# raspi.net
KiCad netlist of a schematic drawn in EAGLE
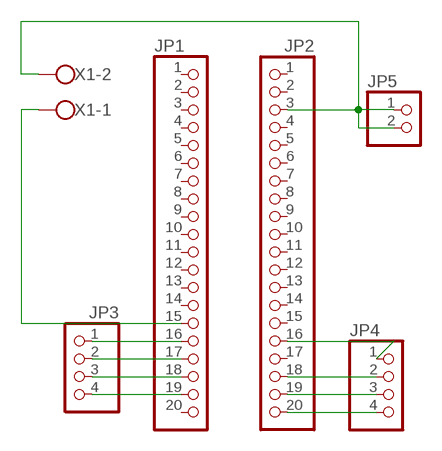
[diagram p0: schematic, sheet 1]

(export (version "E")
  (design (tool "Eeschema 10.0.6"))
  (components
    (comp (ref "JP1")
      (value "PINHD-1X20")
      (footprint "eagle-import:1X20")
      (libsource (lib "eagle-import") (part "PINHD-1X20"))
    )
    (comp (ref "JP2")
      (value "PINHD-1X20")
      (footprint "eagle-import:1X20")
      (libsource (lib "eagle-import") (part "PINHD-1X20"))
    )
    (comp (ref "JP3")
      (value "PINHD-1X4")
      (footprint "eagle-import:1X04")
      (libsource (lib "eagle-import") (part "PINHD-1X4"))
    )
    (comp (ref "JP4")
      (value "PINHD-1X4")
      (footprint "eagle-import:1X04")
      (libsource (lib "eagle-import") (part "PINHD-1X4"))
    )
    (comp (ref "JP5")
      (value "PINHD-1X2")
      (footprint "eagle-import:1X02")
      (libsource (lib "eagle-import") (part "PINHD-1X2"))
    )
    (comp (ref "X1")
      (value "W237-102")
      (footprint "eagle-import:W237-102")
      (fields (field (name "MPN") "237-102"))
      (libsource (lib "eagle-import") (part "W237-102"))
    )
  )
  (nets
    (net (code "1") (name "Net-(JP1-Pad16)") (class "Default")
      (node (ref "JP1") (pin "16") (pinfunction "16_16") (pintype "passive"))
      (node (ref "JP3") (pin "1") (pinfunction "1_1") (pintype "passive"))
    )
    (net (code "2") (name "Net-(JP1-Pad17)") (class "Default")
      (node (ref "JP1") (pin "17") (pinfunction "17_17") (pintype "passive"))
      (node (ref "JP3") (pin "2") (pinfunction "2_2") (pintype "passive"))
    )
    (net (code "3") (name "Net-(JP1-Pad18)") (class "Default")
      (node (ref "JP1") (pin "18") (pinfunction "18_18") (pintype "passive"))
      (node (ref "JP3") (pin "3") (pinfunction "3_3") (pintype "passive"))
    )
    (net (code "4") (name "Net-(JP1-Pad19)") (class "Default")
      (node (ref "JP1") (pin "19") (pinfunction "19_19") (pintype "passive"))
      (node (ref "JP3") (pin "4") (pinfunction "4_4") (pintype "passive"))
    )
    (net (code "5") (name "Net-(JP2-Pad16)") (class "Default")
      (node (ref "JP2") (pin "16") (pinfunction "16_16") (pintype "passive"))
      (node (ref "JP4") (pin "1") (pinfunction "1_1") (pintype "passive"))
    )
    (net (code "6") (name "Net-(JP2-Pad18)") (class "Default")
      (node (ref "JP2") (pin "18") (pinfunction "18_18") (pintype "passive"))
      (node (ref "JP4") (pin "2") (pinfunction "2_2") (pintype "passive"))
    )
    (net (code "7") (name "Net-(JP2-Pad19)") (class "Default")
      (node (ref "JP2") (pin "19") (pinfunction "19_19") (pintype "passive"))
      (node (ref "JP4") (pin "3") (pinfunction "3_3") (pintype "passive"))
    )
    (net (code "8") (name "Net-(JP2-Pad20)") (class "Default")
      (node (ref "JP2") (pin "20") (pinfunction "20_20") (pintype "passive"))
      (node (ref "JP4") (pin "4") (pinfunction "4_4") (pintype "passive"))
    )
    (net (code "9") (name "Net-(X1A-KL)") (class "Default")
      (node (ref "JP1") (pin "15") (pinfunction "15_15") (pintype "passive"))
      (node (ref "X1") (pin "1") (pinfunction "KL_1") (pintype "passive"))
    )
    (net (code "10") (name "Net-(X1B-KL)") (class "Default")
      (node (ref "JP2") (pin "3") (pinfunction "3_3") (pintype "passive"))
      (node (ref "JP5") (pin "1") (pinfunction "1_1") (pintype "passive"))
      (node (ref "JP5") (pin "2") (pinfunction "2_2") (pintype "passive"))
      (node (ref "X1") (pin "2") (pinfunction "KL_2") (pintype "passive"))
    )
    (net (code "11") (name "unconnected-(JP1-Pad1)") (class "Default")
      (node (ref "JP1") (pin "1") (pinfunction "1_1") (pintype "passive"))
    )
    (net (code "12") (name "unconnected-(JP1-Pad2)") (class "Default")
      (node (ref "JP1") (pin "2") (pinfunction "2_2") (pintype "passive"))
    )
    (net (code "13") (name "unconnected-(JP1-Pad3)") (class "Default")
      (node (ref "JP1") (pin "3") (pinfunction "3_3") (pintype "passive"))
    )
    (net (code "14") (name "unconnected-(JP1-Pad4)") (class "Default")
      (node (ref "JP1") (pin "4") (pinfunction "4_4") (pintype "passive"))
    )
    (net (code "15") (name "unconnected-(JP1-Pad5)") (class "Default")
      (node (ref "JP1") (pin "5") (pinfunction "5_5") (pintype "passive"))
    )
    (net (code "16") (name "unconnected-(JP1-Pad6)") (class "Default")
      (node (ref "JP1") (pin "6") (pinfunction "6_6") (pintype "passive"))
    )
    (net (code "17") (name "unconnected-(JP1-Pad7)") (class "Default")
      (node (ref "JP1") (pin "7") (pinfunction "7_7") (pintype "passive"))
    )
    (net (code "18") (name "unconnected-(JP1-Pad8)") (class "Default")
      (node (ref "JP1") (pin "8") (pinfunction "8_8") (pintype "passive"))
    )
    (net (code "19") (name "unconnected-(JP1-Pad9)") (class "Default")
      (node (ref "JP1") (pin "9") (pinfunction "9_9") (pintype "passive"))
    )
    (net (code "20") (name "unconnected-(JP1-Pad10)") (class "Default")
      (node (ref "JP1") (pin "10") (pinfunction "10_10") (pintype "passive"))
    )
    (net (code "21") (name "unconnected-(JP1-Pad11)") (class "Default")
      (node (ref "JP1") (pin "11") (pinfunction "11_11") (pintype "passive"))
    )
    (net (code "22") (name "unconnected-(JP1-Pad12)") (class "Default")
      (node (ref "JP1") (pin "12") (pinfunction "12_12") (pintype "passive"))
    )
    (net (code "23") (name "unconnected-(JP1-Pad13)") (class "Default")
      (node (ref "JP1") (pin "13") (pinfunction "13_13") (pintype "passive"))
    )
    (net (code "24") (name "unconnected-(JP1-Pad14)") (class "Default")
      (node (ref "JP1") (pin "14") (pinfunction "14_14") (pintype "passive"))
    )
    (net (code "25") (name "unconnected-(JP1-Pad20)") (class "Default")
      (node (ref "JP1") (pin "20") (pinfunction "20_20") (pintype "passive"))
    )
    (net (code "26") (name "unconnected-(JP2-Pad1)") (class "Default")
      (node (ref "JP2") (pin "1") (pinfunction "1_1") (pintype "passive"))
    )
    (net (code "27") (name "unconnected-(JP2-Pad2)") (class "Default")
      (node (ref "JP2") (pin "2") (pinfunction "2_2") (pintype "passive"))
    )
    (net (code "28") (name "unconnected-(JP2-Pad4)") (class "Default")
      (node (ref "JP2") (pin "4") (pinfunction "4_4") (pintype "passive"))
    )
    (net (code "29") (name "unconnected-(JP2-Pad5)") (class "Default")
      (node (ref "JP2") (pin "5") (pinfunction "5_5") (pintype "passive"))
    )
    (net (code "30") (name "unconnected-(JP2-Pad6)") (class "Default")
      (node (ref "JP2") (pin "6") (pinfunction "6_6") (pintype "passive"))
    )
    (net (code "31") (name "unconnected-(JP2-Pad7)") (class "Default")
      (node (ref "JP2") (pin "7") (pinfunction "7_7") (pintype "passive"))
    )
    (net (code "32") (name "unconnected-(JP2-Pad8)") (class "Default")
      (node (ref "JP2") (pin "8") (pinfunction "8_8") (pintype "passive"))
    )
    (net (code "33") (name "unconnected-(JP2-Pad9)") (class "Default")
      (node (ref "JP2") (pin "9") (pinfunction "9_9") (pintype "passive"))
    )
    (net (code "34") (name "unconnected-(JP2-Pad10)") (class "Default")
      (node (ref "JP2") (pin "10") (pinfunction "10_10") (pintype "passive"))
    )
    (net (code "35") (name "unconnected-(JP2-Pad11)") (class "Default")
      (node (ref "JP2") (pin "11") (pinfunction "11_11") (pintype "passive"))
    )
    (net (code "36") (name "unconnected-(JP2-Pad12)") (class "Default")
      (node (ref "JP2") (pin "12") (pinfunction "12_12") (pintype "passive"))
    )
    (net (code "37") (name "unconnected-(JP2-Pad13)") (class "Default")
      (node (ref "JP2") (pin "13") (pinfunction "13_13") (pintype "passive"))
    )
    (net (code "38") (name "unconnected-(JP2-Pad14)") (class "Default")
      (node (ref "JP2") (pin "14") (pinfunction "14_14") (pintype "passive"))
    )
    (net (code "39") (name "unconnected-(JP2-Pad15)") (class "Default")
      (node (ref "JP2") (pin "15") (pinfunction "15_15") (pintype "passive"))
    )
    (net (code "40") (name "unconnected-(JP2-Pad17)") (class "Default")
      (node (ref "JP2") (pin "17") (pinfunction "17_17") (pintype "passive"))
    )
  )
)
